# BPC_Clock.net
KiCad netlist of a schematic drawn in Altium Designer
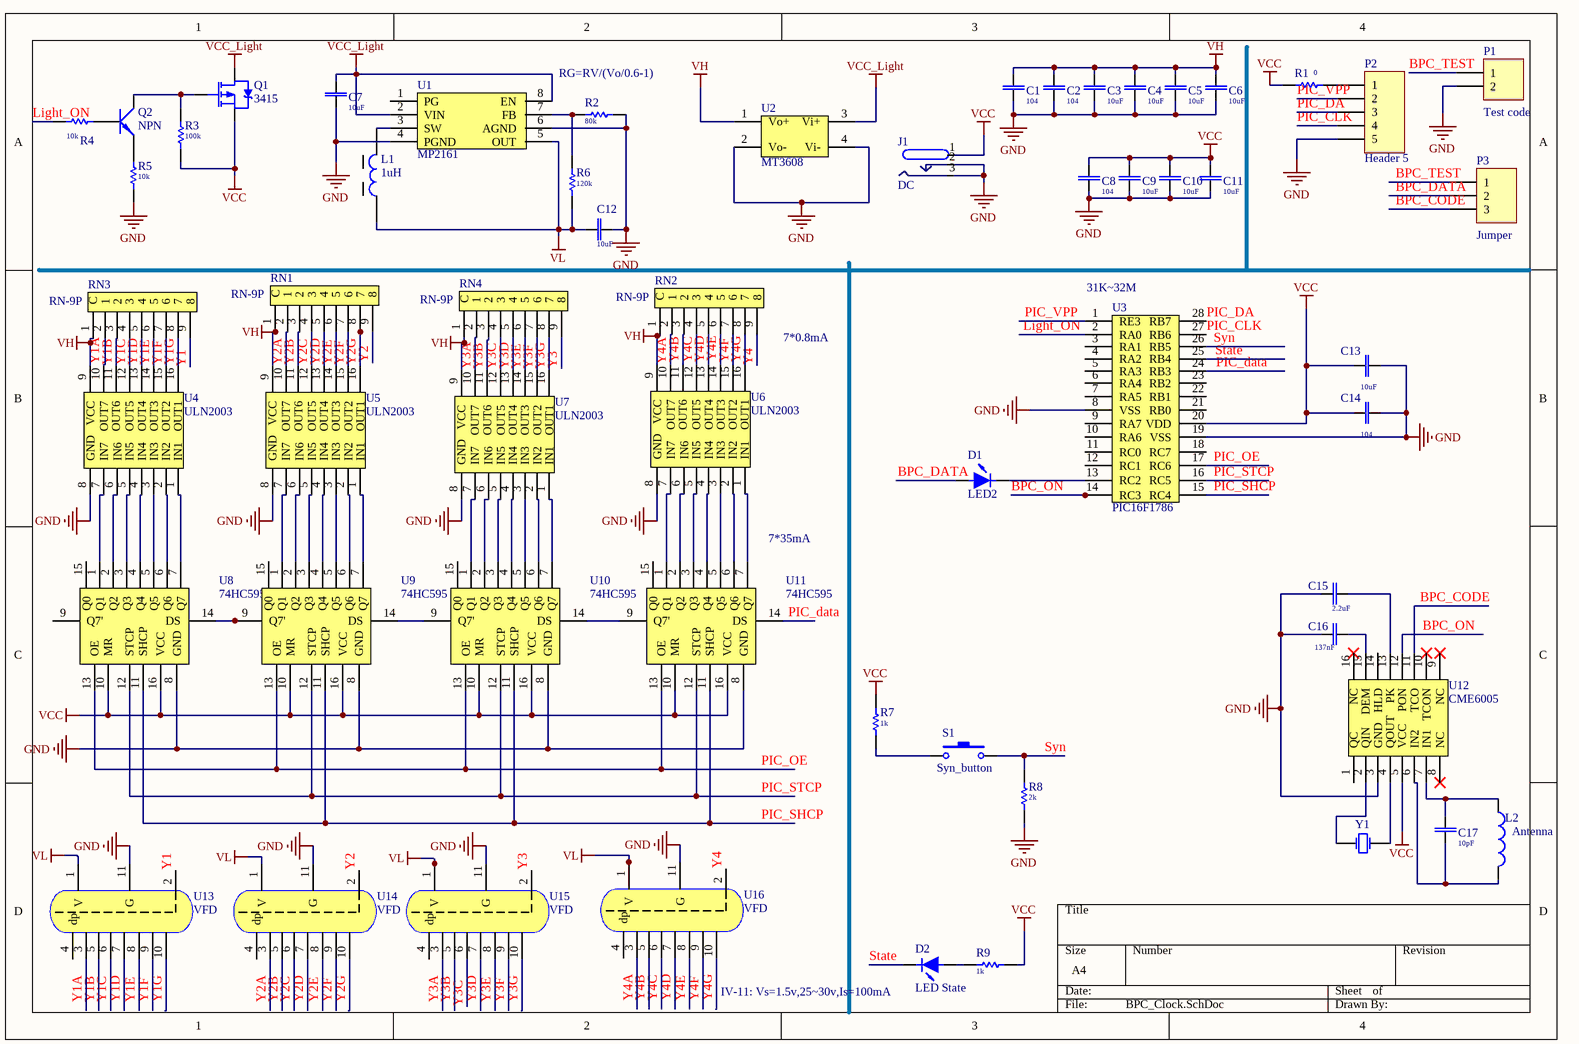
[diagram p0: BPC_Clock.SchDoc]

(export (version "E")
  (design (tool "Eeschema 10.0.6"))
  (components
    (comp (ref "C1")
      (value "104")
      (footprint "CAPC2012N")
      (description "Capacitor")
      (fields (field (name "Comment") "Cap") (field (name "PUBLISHER") "Altium Limited"))
      (libsource (lib "Miscellaneous Devices") (part "Cap"))
    )
    (comp (ref "C2")
      (value "104")
      (footprint "CAPC2012N")
      (description "Capacitor")
      (fields (field (name "Comment") "Cap") (field (name "PUBLISHER") "Altium Limited"))
      (libsource (lib "Miscellaneous Devices") (part "Cap"))
    )
    (comp (ref "C3")
      (value "10uF")
      (footprint "CAPC2012N")
      (description "Capacitor")
      (fields (field (name "Comment") "Cap") (field (name "PUBLISHER") "Altium Limited"))
      (libsource (lib "Miscellaneous Devices") (part "Cap"))
    )
    (comp (ref "C4")
      (value "10uF")
      (footprint "CAPC2012N")
      (description "Capacitor")
      (fields (field (name "Comment") "Cap") (field (name "PUBLISHER") "Altium Limited"))
      (libsource (lib "Miscellaneous Devices") (part "Cap"))
    )
    (comp (ref "C5")
      (value "10uF")
      (footprint "CAPC2012N")
      (description "Capacitor")
      (fields (field (name "Comment") "Cap") (field (name "PUBLISHER") "Altium Limited"))
      (libsource (lib "Miscellaneous Devices") (part "Cap"))
    )
    (comp (ref "C6")
      (value "10uF")
      (footprint "CAPC2012N")
      (description "Capacitor")
      (fields (field (name "Comment") "Cap") (field (name "PUBLISHER") "Altium Limited"))
      (libsource (lib "Miscellaneous Devices") (part "Cap"))
    )
    (comp (ref "C7")
      (value "10uF")
      (footprint "CAPC2012N")
      (description "Capacitor")
      (fields (field (name "Comment") "Cap") (field (name "PUBLISHER") "Altium Limited"))
      (libsource (lib "Miscellaneous Devices") (part "Cap"))
    )
    (comp (ref "C8")
      (value "104")
      (footprint "CAPC2012N")
      (description "Capacitor")
      (fields (field (name "Comment") "Cap") (field (name "PUBLISHER") "Altium Limited"))
      (libsource (lib "Miscellaneous Devices") (part "Cap"))
    )
    (comp (ref "C9")
      (value "10uF")
      (footprint "CAPC2012N")
      (description "Capacitor")
      (fields (field (name "Comment") "Cap") (field (name "PUBLISHER") "Altium Limited"))
      (libsource (lib "Miscellaneous Devices") (part "Cap"))
    )
    (comp (ref "C10")
      (value "10uF")
      (footprint "CAPC2012N")
      (description "Capacitor")
      (fields (field (name "Comment") "Cap") (field (name "PUBLISHER") "Altium Limited"))
      (libsource (lib "Miscellaneous Devices") (part "Cap"))
    )
    (comp (ref "C11")
      (value "10uF")
      (footprint "CAPC2012N")
      (description "Capacitor")
      (fields (field (name "Comment") "Cap") (field (name "PUBLISHER") "Altium Limited"))
      (libsource (lib "Miscellaneous Devices") (part "Cap"))
    )
    (comp (ref "C12")
      (value "10uF")
      (footprint "CAPC2012N")
      (description "Capacitor")
      (fields (field (name "Comment") "Cap") (field (name "PUBLISHER") "Altium Limited"))
      (libsource (lib "Miscellaneous Devices") (part "Cap"))
    )
    (comp (ref "C13")
      (value "10uF")
      (footprint "CAPC2012N")
      (description "Capacitor")
      (fields (field (name "Comment") "Cap") (field (name "PUBLISHER") "Altium Limited"))
      (libsource (lib "Miscellaneous Devices") (part "Cap"))
    )
    (comp (ref "C14")
      (value "104")
      (footprint "CAPC2012N")
      (description "Capacitor")
      (fields (field (name "Comment") "Cap") (field (name "PUBLISHER") "Altium Limited"))
      (libsource (lib "Miscellaneous Devices") (part "Cap"))
    )
    (comp (ref "C15")
      (value "2.2uF")
      (footprint "CAPC2012N")
      (description "Capacitor")
      (fields (field (name "Comment") "Cap") (field (name "PUBLISHER") "Altium Limited"))
      (libsource (lib "Miscellaneous Devices") (part "Cap"))
    )
    (comp (ref "C16")
      (value "137nF")
      (footprint "CAPC2012N")
      (description "Capacitor")
      (fields (field (name "Comment") "Cap") (field (name "PUBLISHER") "Altium Limited"))
      (libsource (lib "Miscellaneous Devices") (part "Cap"))
    )
    (comp (ref "C17")
      (value "10pF")
      (footprint "CAPC2012N")
      (description "Capacitor")
      (fields (field (name "Comment") "Cap") (field (name "PUBLISHER") "Altium Limited"))
      (libsource (lib "Miscellaneous Devices") (part "Cap"))
    )
    (comp (ref "D1")
      (value "LED2")
      (footprint "DSO-F2/D6.1")
      (description "Typical RED, GREEN, YELLOW, AMBER GaAs LED")
      (fields (field (name "PUBLISHER") "Altium Limited"))
      (libsource (lib "Miscellaneous Devices") (part "LED2"))
    )
    (comp (ref "D2")
      (value "LED State")
      (footprint "DSO-F2/D6.1")
      (description "Typical RED, GREEN, YELLOW, AMBER GaAs LED")
      (fields (field (name "PUBLISHER") "Altium Limited"))
      (libsource (lib "Miscellaneous Devices") (part "LED2"))
    )
    (comp (ref "J1") (value "DC") (footprint "DC") (libsource (lib "DC") (part "DC")))
    (comp (ref "L1")
      (value "Chip inductors")
      (footprint "CAPC1608N")
      (fields (field (name "ALTIUM_UNNAMED_1") "1uH"))
      (libsource (lib "Chip inductors") (part "Chip inductors"))
    )
    (comp (ref "L2")
      (value "Antenna")
      (footprint "CAPC2012N")
      (description "Inductor")
      (fields (field (name "PUBLISHER") "Altium Limited"))
      (libsource (lib "Miscellaneous Devices") (part "Inductor"))
    )
    (comp (ref "P1")
      (value "Test code")
      (footprint "HDR1X2")
      (description "Header, 2-Pin")
      (fields (field (name "PUBLISHER") "Altium Limited"))
      (libsource (lib "Miscellaneous Connectors") (part "Header 2"))
    )
    (comp (ref "P2")
      (value "Header 5")
      (footprint "HDR1X5")
      (description "Header, 5-Pin")
      (fields (field (name "PUBLISHER") "Altium Limited"))
      (libsource (lib "Miscellaneous Connectors") (part "Header 5"))
    )
    (comp (ref "P3")
      (value "Jumper")
      (footprint "HDR1X3")
      (description "Header, 3-Pin")
      (fields (field (name "PUBLISHER") "Altium Limited"))
      (libsource (lib "Miscellaneous Connectors") (part "Header 3"))
    )
    (comp (ref "Q1")
      (value "3415")
      (footprint "LC-SOT-23(SOT-23-3)")
      (description "P-Channel Power MOSFET")
      (fields (field (name "PUBLISHER") "Altium Limited"))
      (libsource (lib "Miscellaneous Devices") (part "PMOS-2"))
    )
    (comp (ref "Q2")
      (value "NPN")
      (footprint "BCY-W3")
      (description "NPN Bipolar Transistor")
      (fields (field (name "PUBLISHER") "Altium Limited"))
      (libsource (lib "Miscellaneous Devices") (part "NPN"))
    )
    (comp (ref "R1")
      (value "0")
      (footprint "RES 0805N (2012)")
      (description "Resistor")
      (fields (field (name "PUBLISHER") "Altium Limited"))
      (libsource (lib "Miscellaneous Devices") (part "Res1"))
    )
    (comp (ref "R2")
      (value "80k")
      (footprint "RES 0805N (2012)")
      (description "Resistor")
      (fields (field (name "PUBLISHER") "Altium Limited"))
      (libsource (lib "Miscellaneous Devices") (part "Res1"))
    )
    (comp (ref "R3")
      (value "100k")
      (footprint "RES 0805N (2012)")
      (description "Resistor")
      (fields (field (name "PUBLISHER") "Altium Limited"))
      (libsource (lib "Miscellaneous Devices") (part "Res1"))
    )
    (comp (ref "R4")
      (value "10k")
      (footprint "RES 0805N (2012)")
      (description "Resistor")
      (fields (field (name "PUBLISHER") "Altium Limited"))
      (libsource (lib "Miscellaneous Devices") (part "Res1"))
    )
    (comp (ref "R5")
      (value "10k")
      (footprint "RES 0805N (2012)")
      (description "Resistor")
      (fields (field (name "PUBLISHER") "Altium Limited"))
      (libsource (lib "Miscellaneous Devices") (part "Res1"))
    )
    (comp (ref "R6")
      (value "120k")
      (footprint "RES 0805N (2012)")
      (description "Resistor")
      (fields (field (name "PUBLISHER") "Altium Limited"))
      (libsource (lib "Miscellaneous Devices") (part "Res1"))
    )
    (comp (ref "R7")
      (value "1k")
      (footprint "RES 0805N (2012)")
      (description "Resistor")
      (fields (field (name "PUBLISHER") "Altium Limited"))
      (libsource (lib "Miscellaneous Devices") (part "Res1"))
    )
    (comp (ref "R8")
      (value "2k")
      (footprint "RES 0805N (2012)")
      (description "Resistor")
      (fields (field (name "PUBLISHER") "Altium Limited"))
      (libsource (lib "Miscellaneous Devices") (part "Res1"))
    )
    (comp (ref "R9")
      (value "1k")
      (footprint "RES 0805N (2012)")
      (description "Resistor")
      (fields (field (name "PUBLISHER") "Altium Limited"))
      (libsource (lib "Miscellaneous Devices") (part "Res1"))
    )
    (comp (ref "RN1") (value "RN-9P") (footprint "RN-9P") (libsource (lib "RN-9P") (part "RN-9P")))
    (comp (ref "RN2") (value "RN-9P") (footprint "RN-9P") (libsource (lib "RN-9P") (part "RN-9P")))
    (comp (ref "RN3") (value "RN-9P") (footprint "RN-9P") (libsource (lib "RN-9P") (part "RN-9P")))
    (comp (ref "RN4") (value "RN-9P") (footprint "RN-9P") (libsource (lib "RN-9P") (part "RN-9P")))
    (comp (ref "S1")
      (value "Syn_button")
      (footprint "sw")
      (description "Switch")
      (fields (field (name "PUBLISHER") "Altium Limited"))
      (libsource (lib "Miscellaneous Devices") (part "SW-PB"))
    )
    (comp (ref "U1") (value "MP2161") (footprint "LC-TSOT-23-8") (libsource (lib "MP2161") (part "MP2161")))
    (comp (ref "U2") (value "MT3608") (footprint "MT3608") (libsource (lib "MT3608") (part "MT3608")))
    (comp (ref "U3")
      (value "PIC16F1786")
      (footprint "PIC-28")
      (libsource (lib "PIC16F1786") (part "PIC16F1786"))
    )
    (comp (ref "U4")
      (value "ULN2003")
      (footprint "LC-SOP-16_150mil")
      (libsource (lib "ULN2003") (part "ULN2003"))
    )
    (comp (ref "U5")
      (value "ULN2003")
      (footprint "LC-SOP-16_150mil")
      (libsource (lib "ULN2003") (part "ULN2003"))
    )
    (comp (ref "U6")
      (value "ULN2003")
      (footprint "LC-SOP-16_150mil")
      (libsource (lib "ULN2003") (part "ULN2003"))
    )
    (comp (ref "U7")
      (value "ULN2003")
      (footprint "LC-SOP-16_150mil")
      (libsource (lib "ULN2003") (part "ULN2003"))
    )
    (comp (ref "U8") (value "74HC595") (footprint "LC-DIP-16") (libsource (lib "74HC595") (part "74HC595")))
    (comp (ref "U9") (value "74HC595") (footprint "LC-DIP-16") (libsource (lib "74HC595") (part "74HC595")))
    (comp (ref "U10") (value "74HC595") (footprint "LC-DIP-16") (libsource (lib "74HC595") (part "74HC595")))
    (comp (ref "U11") (value "74HC595") (footprint "LC-DIP-16") (libsource (lib "74HC595") (part "74HC595")))
    (comp (ref "U12") (value "CME6005") (footprint "CME6005") (libsource (lib "CME6005") (part "CME6005")))
    (comp (ref "U13") (value "VFD") (footprint "IV-11") (libsource (lib "VFD") (part "VFD")))
    (comp (ref "U14") (value "VFD") (footprint "IV-11") (libsource (lib "VFD") (part "VFD")))
    (comp (ref "U15") (value "VFD") (footprint "IV-11") (libsource (lib "VFD") (part "VFD")))
    (comp (ref "U16") (value "VFD") (footprint "IV-11") (libsource (lib "VFD") (part "VFD")))
    (comp (ref "Y1")
      (value "XTAL")
      (footprint "BCY-W2/D3.1")
      (description "Crystal Oscillator")
      (fields (field (name "PUBLISHER") "Altium Limited"))
      (libsource (lib "Miscellaneous Devices") (part "XTAL"))
    )
  )
  (nets
    (net (code "1") (name "/BPC_CODE") (class "Default")
      (node (ref "P3") (pin "3") (pinfunction "3_3") (pintype "passive"))
      (node (ref "U12") (pin "11") (pinfunction "TCO_11") (pintype "passive"))
    )
    (net (code "2") (name "/BPC_DATA") (class "Default")
      (node (ref "D1") (pin "1") (pinfunction "A_1") (pintype "passive"))
      (node (ref "P3") (pin "2") (pinfunction "2_2") (pintype "passive"))
    )
    (net (code "3") (name "/BPC_ON") (class "Default")
      (node (ref "U12") (pin "12") (pinfunction "PON_12") (pintype "passive"))
      (node (ref "U3") (pin "14") (pinfunction "RC3_14") (pintype "passive"))
    )
    (net (code "4") (name "/BPC_TEST") (class "Default")
      (node (ref "P1") (pin "1") (pinfunction "1_1") (pintype "passive"))
      (node (ref "P3") (pin "1") (pinfunction "1_1") (pintype "passive"))
    )
    (net (code "5") (name "/Light_ON") (class "Default")
      (node (ref "R4") (pin "1") (pinfunction "1_1") (pintype "passive"))
      (node (ref "U3") (pin "2") (pinfunction "RA0_2") (pintype "passive"))
    )
    (net (code "6") (name "/PIC_CLK") (class "Default")
      (node (ref "P2") (pin "4") (pinfunction "4_4") (pintype "passive"))
      (node (ref "U3") (pin "27") (pinfunction "RB6_27") (pintype "passive"))
    )
    (net (code "7") (name "/PIC_DA") (class "Default")
      (node (ref "P2") (pin "3") (pinfunction "3_3") (pintype "passive"))
      (node (ref "U3") (pin "28") (pinfunction "RB7_28") (pintype "passive"))
    )
    (net (code "8") (name "/PIC_OE") (class "Default")
      (node (ref "U10") (pin "13") (pinfunction "OE_13") (pintype "passive"))
      (node (ref "U11") (pin "13") (pinfunction "OE_13") (pintype "passive"))
      (node (ref "U3") (pin "17") (pinfunction "RC6_17") (pintype "passive"))
      (node (ref "U8") (pin "13") (pinfunction "OE_13") (pintype "passive"))
      (node (ref "U9") (pin "13") (pinfunction "OE_13") (pintype "passive"))
    )
    (net (code "9") (name "/PIC_SHCP") (class "Default")
      (node (ref "U10") (pin "11") (pinfunction "SHCP_11") (pintype "passive"))
      (node (ref "U11") (pin "11") (pinfunction "SHCP_11") (pintype "passive"))
      (node (ref "U3") (pin "15") (pinfunction "RC4_15") (pintype "passive"))
      (node (ref "U8") (pin "11") (pinfunction "SHCP_11") (pintype "passive"))
      (node (ref "U9") (pin "11") (pinfunction "SHCP_11") (pintype "passive"))
    )
    (net (code "10") (name "/PIC_STCP") (class "Default")
      (node (ref "U10") (pin "12") (pinfunction "STCP_12") (pintype "passive"))
      (node (ref "U11") (pin "12") (pinfunction "STCP_12") (pintype "passive"))
      (node (ref "U3") (pin "16") (pinfunction "RC5_16") (pintype "passive"))
      (node (ref "U8") (pin "12") (pinfunction "STCP_12") (pintype "passive"))
      (node (ref "U9") (pin "12") (pinfunction "STCP_12") (pintype "passive"))
    )
    (net (code "11") (name "/PIC_VPP") (class "Default")
      (node (ref "P2") (pin "2") (pinfunction "2_2") (pintype "passive"))
      (node (ref "U3") (pin "1") (pinfunction "RE3_1") (pintype "passive"))
    )
    (net (code "12") (name "/PIC_data") (class "Default")
      (node (ref "U11") (pin "14") (pinfunction "DS_14") (pintype "passive"))
      (node (ref "U3") (pin "24") (pinfunction "RB3_24") (pintype "passive"))
    )
    (net (code "13") (name "/State") (class "Default")
      (node (ref "D2") (pin "2") (pinfunction "K_2") (pintype "passive"))
      (node (ref "U3") (pin "25") (pinfunction "RB4_25") (pintype "passive"))
    )
    (net (code "14") (name "/Syn") (class "Default")
      (node (ref "R8") (pin "2") (pinfunction "2_2") (pintype "passive"))
      (node (ref "S1") (pin "2") (pinfunction "2_2") (pintype "passive"))
      (node (ref "U3") (pin "26") (pinfunction "RB5_26") (pintype "passive"))
    )
    (net (code "15") (name "/Y1") (class "Default")
      (node (ref "RN3") (pin "9") (pinfunction "8_9") (pintype "passive"))
      (node (ref "U13") (pin "2") (pintype "passive"))
    )
    (net (code "16") (name "/Y1A") (class "Default")
      (node (ref "RN3") (pin "2") (pinfunction "1_2") (pintype "passive"))
      (node (ref "U13") (pin "3") (pinfunction "c_3") (pintype "passive"))
      (node (ref "U4") (pin "10") (pinfunction "OUT7_10") (pintype "passive"))
    )
    (net (code "17") (name "/Y1B") (class "Default")
      (node (ref "RN3") (pin "3") (pinfunction "2_3") (pintype "passive"))
      (node (ref "U13") (pin "5") (pinfunction "e_5") (pintype "passive"))
      (node (ref "U4") (pin "11") (pinfunction "OUT6_11") (pintype "passive"))
    )
    (net (code "18") (name "/Y1C") (class "Default")
      (node (ref "RN3") (pin "4") (pinfunction "3_4") (pintype "passive"))
      (node (ref "U13") (pin "6") (pinfunction "f_6") (pintype "passive"))
      (node (ref "U4") (pin "12") (pinfunction "OUT5_12") (pintype "passive"))
    )
    (net (code "19") (name "/Y1D") (class "Default")
      (node (ref "RN3") (pin "5") (pinfunction "4_5") (pintype "passive"))
      (node (ref "U13") (pin "7") (pinfunction "g_7") (pintype "passive"))
      (node (ref "U4") (pin "13") (pinfunction "OUT4_13") (pintype "passive"))
    )
    (net (code "20") (name "/Y1E") (class "Default")
      (node (ref "RN3") (pin "6") (pinfunction "5_6") (pintype "passive"))
      (node (ref "U13") (pin "8") (pinfunction "a_8") (pintype "passive"))
      (node (ref "U4") (pin "14") (pinfunction "OUT3_14") (pintype "passive"))
    )
    (net (code "21") (name "/Y1F") (class "Default")
      (node (ref "RN3") (pin "7") (pinfunction "6_7") (pintype "passive"))
      (node (ref "U13") (pin "9") (pinfunction "b_9") (pintype "passive"))
      (node (ref "U4") (pin "15") (pinfunction "OUT2_15") (pintype "passive"))
    )
    (net (code "22") (name "/Y1G") (class "Default")
      (node (ref "RN3") (pin "8") (pinfunction "7_8") (pintype "passive"))
      (node (ref "U13") (pin "10") (pinfunction "c_10") (pintype "passive"))
      (node (ref "U4") (pin "16") (pinfunction "OUT1_16") (pintype "passive"))
    )
    (net (code "23") (name "/Y2") (class "Default")
      (node (ref "RN1") (pin "9") (pinfunction "8_9") (pintype "passive"))
      (node (ref "U14") (pin "2") (pintype "passive"))
    )
    (net (code "24") (name "/Y2A") (class "Default")
      (node (ref "RN1") (pin "2") (pinfunction "1_2") (pintype "passive"))
      (node (ref "U14") (pin "3") (pinfunction "c_3") (pintype "passive"))
      (node (ref "U5") (pin "10") (pinfunction "OUT7_10") (pintype "passive"))
    )
    (net (code "25") (name "/Y2B") (class "Default")
      (node (ref "RN1") (pin "3") (pinfunction "2_3") (pintype "passive"))
      (node (ref "U14") (pin "5") (pinfunction "e_5") (pintype "passive"))
      (node (ref "U5") (pin "11") (pinfunction "OUT6_11") (pintype "passive"))
    )
    (net (code "26") (name "/Y2C") (class "Default")
      (node (ref "RN1") (pin "4") (pinfunction "3_4") (pintype "passive"))
      (node (ref "U14") (pin "6") (pinfunction "f_6") (pintype "passive"))
      (node (ref "U5") (pin "12") (pinfunction "OUT5_12") (pintype "passive"))
    )
    (net (code "27") (name "/Y2D") (class "Default")
      (node (ref "RN1") (pin "5") (pinfunction "4_5") (pintype "passive"))
      (node (ref "U14") (pin "7") (pinfunction "g_7") (pintype "passive"))
      (node (ref "U5") (pin "13") (pinfunction "OUT4_13") (pintype "passive"))
    )
    (net (code "28") (name "/Y2E") (class "Default")
      (node (ref "RN1") (pin "6") (pinfunction "5_6") (pintype "passive"))
      (node (ref "U14") (pin "8") (pinfunction "a_8") (pintype "passive"))
      (node (ref "U5") (pin "14") (pinfunction "OUT3_14") (pintype "passive"))
    )
    (net (code "29") (name "/Y2F") (class "Default")
      (node (ref "RN1") (pin "7") (pinfunction "6_7") (pintype "passive"))
      (node (ref "U14") (pin "9") (pinfunction "b_9") (pintype "passive"))
      (node (ref "U5") (pin "15") (pinfunction "OUT2_15") (pintype "passive"))
    )
    (net (code "30") (name "/Y2G") (class "Default")
      (node (ref "RN1") (pin "8") (pinfunction "7_8") (pintype "passive"))
      (node (ref "U14") (pin "10") (pinfunction "c_10") (pintype "passive"))
      (node (ref "U5") (pin "16") (pinfunction "OUT1_16") (pintype "passive"))
    )
    (net (code "31") (name "/Y3") (class "Default")
      (node (ref "RN4") (pin "9") (pinfunction "8_9") (pintype "passive"))
      (node (ref "U15") (pin "2") (pintype "passive"))
    )
    (net (code "32") (name "/Y3A") (class "Default")
      (node (ref "RN4") (pin "2") (pinfunction "1_2") (pintype "passive"))
      (node (ref "U15") (pin "3") (pinfunction "c_3") (pintype "passive"))
      (node (ref "U7") (pin "10") (pinfunction "OUT7_10") (pintype "passive"))
    )
    (net (code "33") (name "/Y3B") (class "Default")
      (node (ref "RN4") (pin "3") (pinfunction "2_3") (pintype "passive"))
      (node (ref "U15") (pin "5") (pinfunction "e_5") (pintype "passive"))
      (node (ref "U7") (pin "11") (pinfunction "OUT6_11") (pintype "passive"))
    )
    (net (code "34") (name "/Y3C") (class "Default")
      (node (ref "RN4") (pin "4") (pinfunction "3_4") (pintype "passive"))
      (node (ref "U15") (pin "6") (pinfunction "f_6") (pintype "passive"))
      (node (ref "U7") (pin "12") (pinfunction "OUT5_12") (pintype "passive"))
    )
    (net (code "35") (name "/Y3D") (class "Default")
      (node (ref "RN4") (pin "5") (pinfunction "4_5") (pintype "passive"))
      (node (ref "U15") (pin "7") (pinfunction "g_7") (pintype "passive"))
      (node (ref "U7") (pin "13") (pinfunction "OUT4_13") (pintype "passive"))
    )
    (net (code "36") (name "/Y3E") (class "Default")
      (node (ref "RN4") (pin "6") (pinfunction "5_6") (pintype "passive"))
      (node (ref "U15") (pin "8") (pinfunction "a_8") (pintype "passive"))
      (node (ref "U7") (pin "14") (pinfunction "OUT3_14") (pintype "passive"))
    )
    (net (code "37") (name "/Y3F") (class "Default")
      (node (ref "RN4") (pin "7") (pinfunction "6_7") (pintype "passive"))
      (node (ref "U15") (pin "9") (pinfunction "b_9") (pintype "passive"))
      (node (ref "U7") (pin "15") (pinfunction "OUT2_15") (pintype "passive"))
    )
    (net (code "38") (name "/Y3G") (class "Default")
      (node (ref "RN4") (pin "8") (pinfunction "7_8") (pintype "passive"))
      (node (ref "U15") (pin "10") (pinfunction "c_10") (pintype "passive"))
      (node (ref "U7") (pin "16") (pinfunction "OUT1_16") (pintype "passive"))
    )
    (net (code "39") (name "/Y4") (class "Default")
      (node (ref "RN2") (pin "9") (pinfunction "8_9") (pintype "passive"))
      (node (ref "U16") (pin "2") (pintype "passive"))
    )
    (net (code "40") (name "/Y4A") (class "Default")
      (node (ref "RN2") (pin "2") (pinfunction "1_2") (pintype "passive"))
      (node (ref "U16") (pin "3") (pinfunction "c_3") (pintype "passive"))
      (node (ref "U6") (pin "10") (pinfunction "OUT7_10") (pintype "passive"))
    )
    (net (code "41") (name "/Y4B") (class "Default")
      (node (ref "RN2") (pin "3") (pinfunction "2_3") (pintype "passive"))
      (node (ref "U16") (pin "5") (pinfunction "e_5") (pintype "passive"))
      (node (ref "U6") (pin "11") (pinfunction "OUT6_11") (pintype "passive"))
    )
    (net (code "42") (name "/Y4C") (class "Default")
      (node (ref "RN2") (pin "4") (pinfunction "3_4") (pintype "passive"))
      (node (ref "U16") (pin "6") (pinfunction "f_6") (pintype "passive"))
      (node (ref "U6") (pin "12") (pinfunction "OUT5_12") (pintype "passive"))
    )
    (net (code "43") (name "/Y4D") (class "Default")
      (node (ref "RN2") (pin "5") (pinfunction "4_5") (pintype "passive"))
      (node (ref "U16") (pin "7") (pinfunction "g_7") (pintype "passive"))
      (node (ref "U6") (pin "13") (pinfunction "OUT4_13") (pintype "passive"))
    )
    (net (code "44") (name "/Y4E") (class "Default")
      (node (ref "RN2") (pin "6") (pinfunction "5_6") (pintype "passive"))
      (node (ref "U16") (pin "8") (pinfunction "a_8") (pintype "passive"))
      (node (ref "U6") (pin "14") (pinfunction "OUT3_14") (pintype "passive"))
    )
    (net (code "45") (name "/Y4F") (class "Default")
      (node (ref "RN2") (pin "7") (pinfunction "6_7") (pintype "passive"))
      (node (ref "U16") (pin "9") (pinfunction "b_9") (pintype "passive"))
      (node (ref "U6") (pin "15") (pinfunction "OUT2_15") (pintype "passive"))
    )
    (net (code "46") (name "/Y4G") (class "Default")
      (node (ref "RN2") (pin "8") (pinfunction "7_8") (pintype "passive"))
      (node (ref "U16") (pin "10") (pinfunction "c_10") (pintype "passive"))
      (node (ref "U6") (pin "16") (pinfunction "OUT1_16") (pintype "passive"))
    )
    (net (code "47") (name "GND") (class "Default")
      (node (ref "C1") (pin "2") (pinfunction "2_2") (pintype "passive"))
      (node (ref "C10") (pin "2") (pinfunction "2_2") (pintype "passive"))
      (node (ref "C11") (pin "2") (pinfunction "2_2") (pintype "passive"))
      (node (ref "C12") (pin "2") (pinfunction "2_2") (pintype "passive"))
      (node (ref "C13") (pin "2") (pinfunction "2_2") (pintype "passive"))
      (node (ref "C14") (pin "2") (pinfunction "2_2") (pintype "passive"))
      (node (ref "C15") (pin "2") (pinfunction "2_2") (pintype "passive"))
      (node (ref "C16") (pin "2") (pinfunction "2_2") (pintype "passive"))
      (node (ref "C2") (pin "2") (pinfunction "2_2") (pintype "passive"))
      (node (ref "C3") (pin "2") (pinfunction "2_2") (pintype "passive"))
      (node (ref "C4") (pin "2") (pinfunction "2_2") (pintype "passive"))
      (node (ref "C5") (pin "2") (pinfunction "2_2") (pintype "passive"))
      (node (ref "C6") (pin "2") (pinfunction "2_2") (pintype "passive"))
      (node (ref "C7") (pin "2") (pinfunction "2_2") (pintype "passive"))
      (node (ref "C8") (pin "2") (pinfunction "2_2") (pintype "passive"))
      (node (ref "C9") (pin "2") (pinfunction "2_2") (pintype "passive"))
      (node (ref "J1") (pin "2") (pinfunction "10_2") (pintype "passive"))
      (node (ref "J1") (pin "3") (pinfunction "11_3") (pintype "passive"))
      (node (ref "P1") (pin "2") (pinfunction "2_2") (pintype "passive"))
      (node (ref "P2") (pin "5") (pinfunction "5_5") (pintype "passive"))
      (node (ref "R2") (pin "1") (pinfunction "1_1") (pintype "passive"))
      (node (ref "R5") (pin "1") (pinfunction "1_1") (pintype "passive"))
      (node (ref "R8") (pin "1") (pinfunction "1_1") (pintype "passive"))
      (node (ref "U1") (pin "4") (pinfunction "PGND_4") (pintype "passive"))
      (node (ref "U1") (pin "6") (pinfunction "AGND_6") (pintype "passive"))
      (node (ref "U10") (pin "8") (pinfunction "GND_8") (pintype "passive"))
      (node (ref "U11") (pin "8") (pinfunction "GND_8") (pintype "passive"))
      (node (ref "U12") (pin "3") (pinfunction "GND_3") (pintype "passive"))
      (node (ref "U13") (pin "11") (pinfunction "G_11") (pintype "passive"))
      (node (ref "U14") (pin "11") (pinfunction "G_11") (pintype "passive"))
      (node (ref "U15") (pin "11") (pinfunction "G_11") (pintype "passive"))
      (node (ref "U16") (pin "11") (pinfunction "G_11") (pintype "passive"))
      (node (ref "U2") (pin "2") (pinfunction "Vo-_2") (pintype "passive"))
      (node (ref "U2") (pin "4") (pinfunction "Vi-_4") (pintype "passive"))
      (node (ref "U3") (pin "19") (pinfunction "VSS_19") (pintype "passive"))
      (node (ref "U3") (pin "8") (pinfunction "VSS_8") (pintype "passive"))
      (node (ref "U4") (pin "8") (pinfunction "GND_8") (pintype "passive"))
      (node (ref "U5") (pin "8") (pinfunction "GND_8") (pintype "passive"))
      (node (ref "U6") (pin "8") (pinfunction "GND_8") (pintype "passive"))
      (node (ref "U7") (pin "8") (pinfunction "GND_8") (pintype "passive"))
      (node (ref "U8") (pin "8") (pinfunction "GND_8") (pintype "passive"))
      (node (ref "U9") (pin "8") (pinfunction "GND_8") (pintype "passive"))
    )
    (net (code "48") (name "Net-(D1-K)") (class "Default")
      (node (ref "D1") (pin "2") (pinfunction "K_2") (pintype "passive"))
      (node (ref "U3") (pin "13") (pinfunction "RC2_13") (pintype "passive"))
    )
    (net (code "49") (name "Net-(D2-A)") (class "Default")
      (node (ref "D2") (pin "1") (pinfunction "A_1") (pintype "passive"))
      (node (ref "R9") (pin "1") (pinfunction "1_1") (pintype "passive"))
    )
    (net (code "50") (name "Net-(P2-Pad1)") (class "Default")
      (node (ref "P2") (pin "1") (pinfunction "1_1") (pintype "passive"))
      (node (ref "R1") (pin "1") (pinfunction "1_1") (pintype "passive"))
    )
    (net (code "51") (name "Net-(Q1-G)") (class "Default")
      (node (ref "Q1") (pin "1") (pinfunction "G_1") (pintype "passive"))
      (node (ref "Q2") (pin "1") (pinfunction "C_1") (pintype "passive"))
      (node (ref "R3") (pin "2") (pinfunction "2_2") (pintype "passive"))
    )
    (net (code "52") (name "Net-(Q2-B)") (class "Default")
      (node (ref "Q2") (pin "2") (pinfunction "B_2") (pintype "passive"))
      (node (ref "R4") (pin "2") (pinfunction "2_2") (pintype "passive"))
    )
    (net (code "53") (name "Net-(Q2-E)") (class "Default")
      (node (ref "Q2") (pin "3") (pinfunction "E_3") (pintype "passive"))
      (node (ref "R5") (pin "2") (pinfunction "2_2") (pintype "passive"))
    )
    (net (code "54") (name "Net-(R7-Pad1)") (class "Default")
      (node (ref "R7") (pin "1") (pinfunction "1_1") (pintype "passive"))
      (node (ref "S1") (pin "1") (pinfunction "1_1") (pintype "passive"))
    )
    (net (code "55") (name "Net-(U1-FB)") (class "Default")
      (node (ref "R2") (pin "2") (pinfunction "2_2") (pintype "passive"))
      (node (ref "R6") (pin "1") (pinfunction "1_1") (pintype "passive"))
      (node (ref "U1") (pin "7") (pinfunction "FB_7") (pintype "passive"))
    )
    (net (code "56") (name "Net-(U1-SW)") (class "Default")
      (node (ref "L1") (pin "2") (pinfunction "2_2") (pintype "passive"))
      (node (ref "U1") (pin "3") (pinfunction "SW_3") (pintype "passive"))
    )
    (net (code "57") (name "Net-(U4-IN1)") (class "Default")
      (node (ref "U4") (pin "1") (pinfunction "IN1_1") (pintype "passive"))
      (node (ref "U8") (pin "7") (pinfunction "Q7_7") (pintype "passive"))
    )
    (net (code "58") (name "Net-(U4-IN2)") (class "Default")
      (node (ref "U4") (pin "2") (pinfunction "IN2_2") (pintype "passive"))
      (node (ref "U8") (pin "6") (pinfunction "Q6_6") (pintype "passive"))
    )
    (net (code "59") (name "Net-(U4-IN3)") (class "Default")
      (node (ref "U4") (pin "3") (pinfunction "IN3_3") (pintype "passive"))
      (node (ref "U8") (pin "5") (pinfunction "Q5_5") (pintype "passive"))
    )
    (net (code "60") (name "Net-(U4-IN4)") (class "Default")
      (node (ref "U4") (pin "4") (pinfunction "IN4_4") (pintype "passive"))
      (node (ref "U8") (pin "4") (pinfunction "Q4_4") (pintype "passive"))
    )
    (net (code "61") (name "Net-(U4-IN5)") (class "Default")
      (node (ref "U4") (pin "5") (pinfunction "IN5_5") (pintype "passive"))
      (node (ref "U8") (pin "3") (pinfunction "Q3_3") (pintype "passive"))
    )
    (net (code "62") (name "Net-(U4-IN6)") (class "Default")
      (node (ref "U4") (pin "6") (pinfunction "IN6_6") (pintype "passive"))
      (node (ref "U8") (pin "2") (pinfunction "Q2_2") (pintype "passive"))
    )
    (net (code "63") (name "Net-(U4-IN7)") (class "Default")
      (node (ref "U4") (pin "7") (pinfunction "IN7_7") (pintype "passive"))
      (node (ref "U8") (pin "1") (pinfunction "Q1_1") (pintype "passive"))
    )
    (net (code "64") (name "Net-(U5-IN1)") (class "Default")
      (node (ref "U5") (pin "1") (pinfunction "IN1_1") (pintype "passive"))
      (node (ref "U9") (pin "7") (pinfunction "Q7_7") (pintype "passive"))
    )
    (net (code "65") (name "Net-(U5-IN2)") (class "Default")
      (node (ref "U5") (pin "2") (pinfunction "IN2_2") (pintype "passive"))
      (node (ref "U9") (pin "6") (pinfunction "Q6_6") (pintype "passive"))
    )
    (net (code "66") (name "Net-(U5-IN3)") (class "Default")
      (node (ref "U5") (pin "3") (pinfunction "IN3_3") (pintype "passive"))
      (node (ref "U9") (pin "5") (pinfunction "Q5_5") (pintype "passive"))
    )
    (net (code "67") (name "Net-(U5-IN4)") (class "Default")
      (node (ref "U5") (pin "4") (pinfunction "IN4_4") (pintype "passive"))
      (node (ref "U9") (pin "4") (pinfunction "Q4_4") (pintype "passive"))
    )
    (net (code "68") (name "Net-(U5-IN5)") (class "Default")
      (node (ref "U5") (pin "5") (pinfunction "IN5_5") (pintype "passive"))
      (node (ref "U9") (pin "3") (pinfunction "Q3_3") (pintype "passive"))
    )
    (net (code "69") (name "Net-(U5-IN6)") (class "Default")
      (node (ref "U5") (pin "6") (pinfunction "IN6_6") (pintype "passive"))
      (node (ref "U9") (pin "2") (pinfunction "Q2_2") (pintype "passive"))
    )
    (net (code "70") (name "Net-(U5-IN7)") (class "Default")
      (node (ref "U5") (pin "7") (pinfunction "IN7_7") (pintype "passive"))
      (node (ref "U9") (pin "1") (pinfunction "Q1_1") (pintype "passive"))
    )
    (net (code "71") (name "Net-(U8-DS)") (class "Default")
      (node (ref "U8") (pin "14") (pinfunction "DS_14") (pintype "passive"))
      (node (ref "U9") (pin "9") (pinfunction "Q7'_9") (pintype "passive"))
    )
    (net (code "72") (name "Net-(U10-DS)") (class "Default")
      (node (ref "U10") (pin "14") (pinfunction "DS_14") (pintype "passive"))
      (node (ref "U11") (pin "9") (pinfunction "Q7'_9") (pintype "passive"))
    )
    (net (code "73") (name "Net-(U10-Q1)") (class "Default")
      (node (ref "U10") (pin "1") (pinfunction "Q1_1") (pintype "passive"))
      (node (ref "U7") (pin "7") (pinfunction "IN7_7") (pintype "passive"))
    )
    (net (code "74") (name "Net-(U10-Q2)") (class "Default")
      (node (ref "U10") (pin "2") (pinfunction "Q2_2") (pintype "passive"))
      (node (ref "U7") (pin "6") (pinfunction "IN6_6") (pintype "passive"))
    )
    (net (code "75") (name "Net-(U10-Q3)") (class "Default")
      (node (ref "U10") (pin "3") (pinfunction "Q3_3") (pintype "passive"))
      (node (ref "U7") (pin "5") (pinfunction "IN5_5") (pintype "passive"))
    )
    (net (code "76") (name "Net-(U10-Q4)") (class "Default")
      (node (ref "U10") (pin "4") (pinfunction "Q4_4") (pintype "passive"))
      (node (ref "U7") (pin "4") (pinfunction "IN4_4") (pintype "passive"))
    )
    (net (code "77") (name "Net-(U10-Q5)") (class "Default")
      (node (ref "U10") (pin "5") (pinfunction "Q5_5") (pintype "passive"))
      (node (ref "U7") (pin "3") (pinfunction "IN3_3") (pintype "passive"))
    )
    (net (code "78") (name "Net-(U10-Q6)") (class "Default")
      (node (ref "U10") (pin "6") (pinfunction "Q6_6") (pintype "passive"))
      (node (ref "U7") (pin "2") (pinfunction "IN2_2") (pintype "passive"))
    )
    (net (code "79") (name "Net-(U10-Q7')") (class "Default")
      (node (ref "U10") (pin "9") (pinfunction "Q7'_9") (pintype "passive"))
      (node (ref "U9") (pin "14") (pinfunction "DS_14") (pintype "passive"))
    )
    (net (code "80") (name "Net-(U10-Q7)") (class "Default")
      (node (ref "U10") (pin "7") (pinfunction "Q7_7") (pintype "passive"))
      (node (ref "U7") (pin "1") (pinfunction "IN1_1") (pintype "passive"))
    )
    (net (code "81") (name "Net-(U11-Q1)") (class "Default")
      (node (ref "U11") (pin "1") (pinfunction "Q1_1") (pintype "passive"))
      (node (ref "U6") (pin "7") (pinfunction "IN7_7") (pintype "passive"))
    )
    (net (code "82") (name "Net-(U11-Q2)") (class "Default")
      (node (ref "U11") (pin "2") (pinfunction "Q2_2") (pintype "passive"))
      (node (ref "U6") (pin "6") (pinfunction "IN6_6") (pintype "passive"))
    )
    (net (code "83") (name "Net-(U11-Q3)") (class "Default")
      (node (ref "U11") (pin "3") (pinfunction "Q3_3") (pintype "passive"))
      (node (ref "U6") (pin "5") (pinfunction "IN5_5") (pintype "passive"))
    )
    (net (code "84") (name "Net-(U11-Q4)") (class "Default")
      (node (ref "U11") (pin "4") (pinfunction "Q4_4") (pintype "passive"))
      (node (ref "U6") (pin "4") (pinfunction "IN4_4") (pintype "passive"))
    )
    (net (code "85") (name "Net-(U11-Q5)") (class "Default")
      (node (ref "U11") (pin "5") (pinfunction "Q5_5") (pintype "passive"))
      (node (ref "U6") (pin "3") (pinfunction "IN3_3") (pintype "passive"))
    )
    (net (code "86") (name "Net-(U11-Q6)") (class "Default")
      (node (ref "U11") (pin "6") (pinfunction "Q6_6") (pintype "passive"))
      (node (ref "U6") (pin "2") (pinfunction "IN2_2") (pintype "passive"))
    )
    (net (code "87") (name "Net-(U11-Q7)") (class "Default")
      (node (ref "U11") (pin "7") (pinfunction "Q7_7") (pintype "passive"))
      (node (ref "U6") (pin "1") (pinfunction "IN1_1") (pintype "passive"))
    )
    (net (code "88") (name "Net-(U12-DEM)") (class "Default")
      (node (ref "C16") (pin "1") (pinfunction "1_1") (pintype "passive"))
      (node (ref "U12") (pin "15") (pinfunction "DEM_15") (pintype "passive"))
    )
    (net (code "89") (name "Net-(U12-IN1)") (class "Default")
      (node (ref "C17") (pin "1") (pinfunction "1_1") (pintype "passive"))
      (node (ref "L2") (pin "1") (pinfunction "1_1") (pintype "passive"))
      (node (ref "U12") (pin "7") (pinfunction "IN1_7") (pintype "passive"))
    )
    (net (code "90") (name "Net-(U12-IN2)") (class "Default")
      (node (ref "C17") (pin "2") (pinfunction "2_2") (pintype "passive"))
      (node (ref "L2") (pin "2") (pinfunction "2_2") (pintype "passive"))
      (node (ref "U12") (pin "6") (pinfunction "IN2_6") (pintype "passive"))
    )
    (net (code "91") (name "Net-(U12-PK)") (class "Default")
      (node (ref "C15") (pin "1") (pinfunction "1_1") (pintype "passive"))
      (node (ref "U12") (pin "13") (pinfunction "PK_13") (pintype "passive"))
    )
    (net (code "92") (name "Net-(U12-QIN)") (class "Default")
      (node (ref "U12") (pin "2") (pinfunction "QIN_2") (pintype "passive"))
      (node (ref "Y1") (pin "1") (pinfunction "OSC1_1") (pintype "passive"))
    )
    (net (code "93") (name "Net-(U12-QOUT)") (class "Default")
      (node (ref "U12") (pin "4") (pinfunction "QOUT_4") (pintype "passive"))
      (node (ref "Y1") (pin "2") (pinfunction "OSC2_2") (pintype "passive"))
    )
    (net (code "94") (name "VCC") (class "Default")
      (node (ref "C10") (pin "1") (pinfunction "1_1") (pintype "passive"))
      (node (ref "C11") (pin "1") (pinfunction "1_1") (pintype "passive"))
      (node (ref "C13") (pin "1") (pinfunction "1_1") (pintype "passive"))
      (node (ref "C14") (pin "1") (pinfunction "1_1") (pintype "passive"))
      (node (ref "C8") (pin "1") (pinfunction "1_1") (pintype "passive"))
      (node (ref "C9") (pin "1") (pinfunction "1_1") (pintype "passive"))
      (node (ref "J1") (pin "1") (pinfunction "9_1") (pintype "passive"))
      (node (ref "Q1") (pin "3") (pinfunction "S_3") (pintype "passive"))
      (node (ref "R1") (pin "2") (pinfunction "2_2") (pintype "passive"))
      (node (ref "R3") (pin "1") (pinfunction "1_1") (pintype "passive"))
      (node (ref "R7") (pin "2") (pinfunction "2_2") (pintype "passive"))
      (node (ref "R9") (pin "2") (pinfunction "2_2") (pintype "passive"))
      (node (ref "U10") (pin "10") (pinfunction "MR_10") (pintype "passive"))
      (node (ref "U10") (pin "16") (pinfunction "VCC_16") (pintype "passive"))
      (node (ref "U11") (pin "10") (pinfunction "MR_10") (pintype "passive"))
      (node (ref "U11") (pin "16") (pinfunction "VCC_16") (pintype "passive"))
      (node (ref "U12") (pin "5") (pinfunction "VCC_5") (pintype "passive"))
      (node (ref "U3") (pin "20") (pinfunction "VDD_20") (pintype "passive"))
      (node (ref "U8") (pin "10") (pinfunction "MR_10") (pintype "passive"))
      (node (ref "U8") (pin "16") (pinfunction "VCC_16") (pintype "passive"))
      (node (ref "U9") (pin "10") (pinfunction "MR_10") (pintype "passive"))
      (node (ref "U9") (pin "16") (pinfunction "VCC_16") (pintype "passive"))
    )
    (net (code "95") (name "VCC_Light") (class "Default")
      (node (ref "C7") (pin "1") (pinfunction "1_1") (pintype "passive"))
      (node (ref "Q1") (pin "2") (pinfunction "D_2") (pintype "passive"))
      (node (ref "U1") (pin "2") (pinfunction "VIN_2") (pintype "passive"))
      (node (ref "U1") (pin "8") (pinfunction "EN_8") (pintype "passive"))
      (node (ref "U2") (pin "3") (pinfunction "Vi+_3") (pintype "passive"))
    )
    (net (code "96") (name "VH") (class "Default")
      (node (ref "C1") (pin "1") (pinfunction "1_1") (pintype "passive"))
      (node (ref "C2") (pin "1") (pinfunction "1_1") (pintype "passive"))
      (node (ref "C3") (pin "1") (pinfunction "1_1") (pintype "passive"))
      (node (ref "C4") (pin "1") (pinfunction "1_1") (pintype "passive"))
      (node (ref "C5") (pin "1") (pinfunction "1_1") (pintype "passive"))
      (node (ref "C6") (pin "1") (pinfunction "1_1") (pintype "passive"))
      (node (ref "RN1") (pin "1") (pinfunction "C_1") (pintype "passive"))
      (node (ref "RN2") (pin "1") (pinfunction "C_1") (pintype "passive"))
      (node (ref "RN3") (pin "1") (pinfunction "C_1") (pintype "passive"))
      (node (ref "RN4") (pin "1") (pinfunction "C_1") (pintype "passive"))
      (node (ref "U2") (pin "1") (pinfunction "Vo+_1") (pintype "passive"))
      (node (ref "U4") (pin "9") (pinfunction "VCC_9") (pintype "passive"))
      (node (ref "U5") (pin "9") (pinfunction "VCC_9") (pintype "passive"))
      (node (ref "U6") (pin "9") (pinfunction "VCC_9") (pintype "passive"))
      (node (ref "U7") (pin "9") (pinfunction "VCC_9") (pintype "passive"))
    )
    (net (code "97") (name "VL") (class "Default")
      (node (ref "C12") (pin "1") (pinfunction "1_1") (pintype "passive"))
      (node (ref "L1") (pin "1") (pinfunction "1_1") (pintype "passive"))
      (node (ref "R6") (pin "2") (pinfunction "2_2") (pintype "passive"))
      (node (ref "U1") (pin "5") (pinfunction "OUT_5") (pintype "passive"))
      (node (ref "U13") (pin "1") (pinfunction "V_1") (pintype "passive"))
      (node (ref "U14") (pin "1") (pinfunction "V_1") (pintype "passive"))
      (node (ref "U15") (pin "1") (pinfunction "V_1") (pintype "passive"))
      (node (ref "U16") (pin "1") (pinfunction "V_1") (pintype "passive"))
    )
    (net (code "98") (name "unconnected-(U1-PG-Pad1)") (class "Default")
      (node (ref "U1") (pin "1") (pinfunction "PG_1") (pintype "passive"))
    )
    (net (code "99") (name "unconnected-(U3-RA1-Pad3)") (class "Default")
      (node (ref "U3") (pin "3") (pinfunction "RA1_3") (pintype "passive"))
    )
    (net (code "100") (name "unconnected-(U3-RA2-Pad4)") (class "Default")
      (node (ref "U3") (pin "4") (pinfunction "RA2_4") (pintype "passive"))
    )
    (net (code "101") (name "unconnected-(U3-RA3-Pad5)") (class "Default")
      (node (ref "U3") (pin "5") (pinfunction "RA3_5") (pintype "passive"))
    )
    (net (code "102") (name "unconnected-(U3-RA4-Pad6)") (class "Default")
      (node (ref "U3") (pin "6") (pinfunction "RA4_6") (pintype "passive"))
    )
    (net (code "103") (name "unconnected-(U3-RA5-Pad7)") (class "Default")
      (node (ref "U3") (pin "7") (pinfunction "RA5_7") (pintype "passive"))
    )
    (net (code "104") (name "unconnected-(U3-RA6-Pad10)") (class "Default")
      (node (ref "U3") (pin "10") (pinfunction "RA6_10") (pintype "passive"))
    )
    (net (code "105") (name "unconnected-(U3-RA7-Pad9)") (class "Default")
      (node (ref "U3") (pin "9") (pinfunction "RA7_9") (pintype "passive"))
    )
    (net (code "106") (name "unconnected-(U3-RB0-Pad21)") (class "Default")
      (node (ref "U3") (pin "21") (pinfunction "RB0_21") (pintype "passive"))
    )
    (net (code "107") (name "unconnected-(U3-RB1-Pad22)") (class "Default")
      (node (ref "U3") (pin "22") (pinfunction "RB1_22") (pintype "passive"))
    )
    (net (code "108") (name "unconnected-(U3-RB2-Pad23)") (class "Default")
      (node (ref "U3") (pin "23") (pinfunction "RB2_23") (pintype "passive"))
    )
    (net (code "109") (name "unconnected-(U3-RC0-Pad11)") (class "Default")
      (node (ref "U3") (pin "11") (pinfunction "RC0_11") (pintype "passive"))
    )
    (net (code "110") (name "unconnected-(U3-RC1-Pad12)") (class "Default")
      (node (ref "U3") (pin "12") (pinfunction "RC1_12") (pintype "passive"))
    )
    (net (code "111") (name "unconnected-(U3-RC7-Pad18)") (class "Default")
      (node (ref "U3") (pin "18") (pinfunction "RC7_18") (pintype "passive"))
    )
    (net (code "112") (name "unconnected-(U8-Q0-Pad15)") (class "Default")
      (node (ref "U8") (pin "15") (pinfunction "Q0_15") (pintype "passive"))
    )
    (net (code "113") (name "unconnected-(U8-Q7'-Pad9)") (class "Default")
      (node (ref "U8") (pin "9") (pinfunction "Q7'_9") (pintype "passive"))
    )
    (net (code "114") (name "unconnected-(U9-Q0-Pad15)") (class "Default")
      (node (ref "U9") (pin "15") (pinfunction "Q0_15") (pintype "passive"))
    )
    (net (code "115") (name "unconnected-(U10-Q0-Pad15)") (class "Default")
      (node (ref "U10") (pin "15") (pinfunction "Q0_15") (pintype "passive"))
    )
    (net (code "116") (name "unconnected-(U11-Q0-Pad15)") (class "Default")
      (node (ref "U11") (pin "15") (pinfunction "Q0_15") (pintype "passive"))
    )
    (net (code "117") (name "unconnected-(U12-HLD-Pad14)") (class "Default")
      (node (ref "U12") (pin "14") (pinfunction "HLD_14") (pintype "passive"))
    )
    (net (code "118") (name "unconnected-(U12-NC-Pad8)") (class "Default")
      (node (ref "U12") (pin "8") (pinfunction "NC_8") (pintype "passive+no_connect"))
    )
    (net (code "119") (name "unconnected-(U12-NC-Pad9)") (class "Default")
      (node (ref "U12") (pin "9") (pinfunction "NC_9") (pintype "passive+no_connect"))
    )
    (net (code "120") (name "unconnected-(U12-NC-Pad16)") (class "Default")
      (node (ref "U12") (pin "16") (pinfunction "NC_16") (pintype "passive+no_connect"))
    )
    (net (code "121") (name "unconnected-(U12-QC-Pad1)") (class "Default")
      (node (ref "U12") (pin "1") (pinfunction "QC_1") (pintype "passive"))
    )
    (net (code "122") (name "unconnected-(U12-TCON-Pad10)") (class "Default")
      (node (ref "U12") (pin "10") (pinfunction "TCON_10") (pintype "passive+no_connect"))
    )
    (net (code "123") (name "unconnected-(U13-dp-Pad4)") (class "Default")
      (node (ref "U13") (pin "4") (pinfunction "dp_4") (pintype "passive"))
    )
    (net (code "124") (name "unconnected-(U14-dp-Pad4)") (class "Default")
      (node (ref "U14") (pin "4") (pinfunction "dp_4") (pintype "passive"))
    )
    (net (code "125") (name "unconnected-(U15-dp-Pad4)") (class "Default")
      (node (ref "U15") (pin "4") (pinfunction "dp_4") (pintype "passive"))
    )
    (net (code "126") (name "unconnected-(U16-dp-Pad4)") (class "Default")
      (node (ref "U16") (pin "4") (pinfunction "dp_4") (pintype "passive"))
    )
  )
)
